# 24GSchematic.net
KiCad netlist of a schematic drawn in Altium Designer
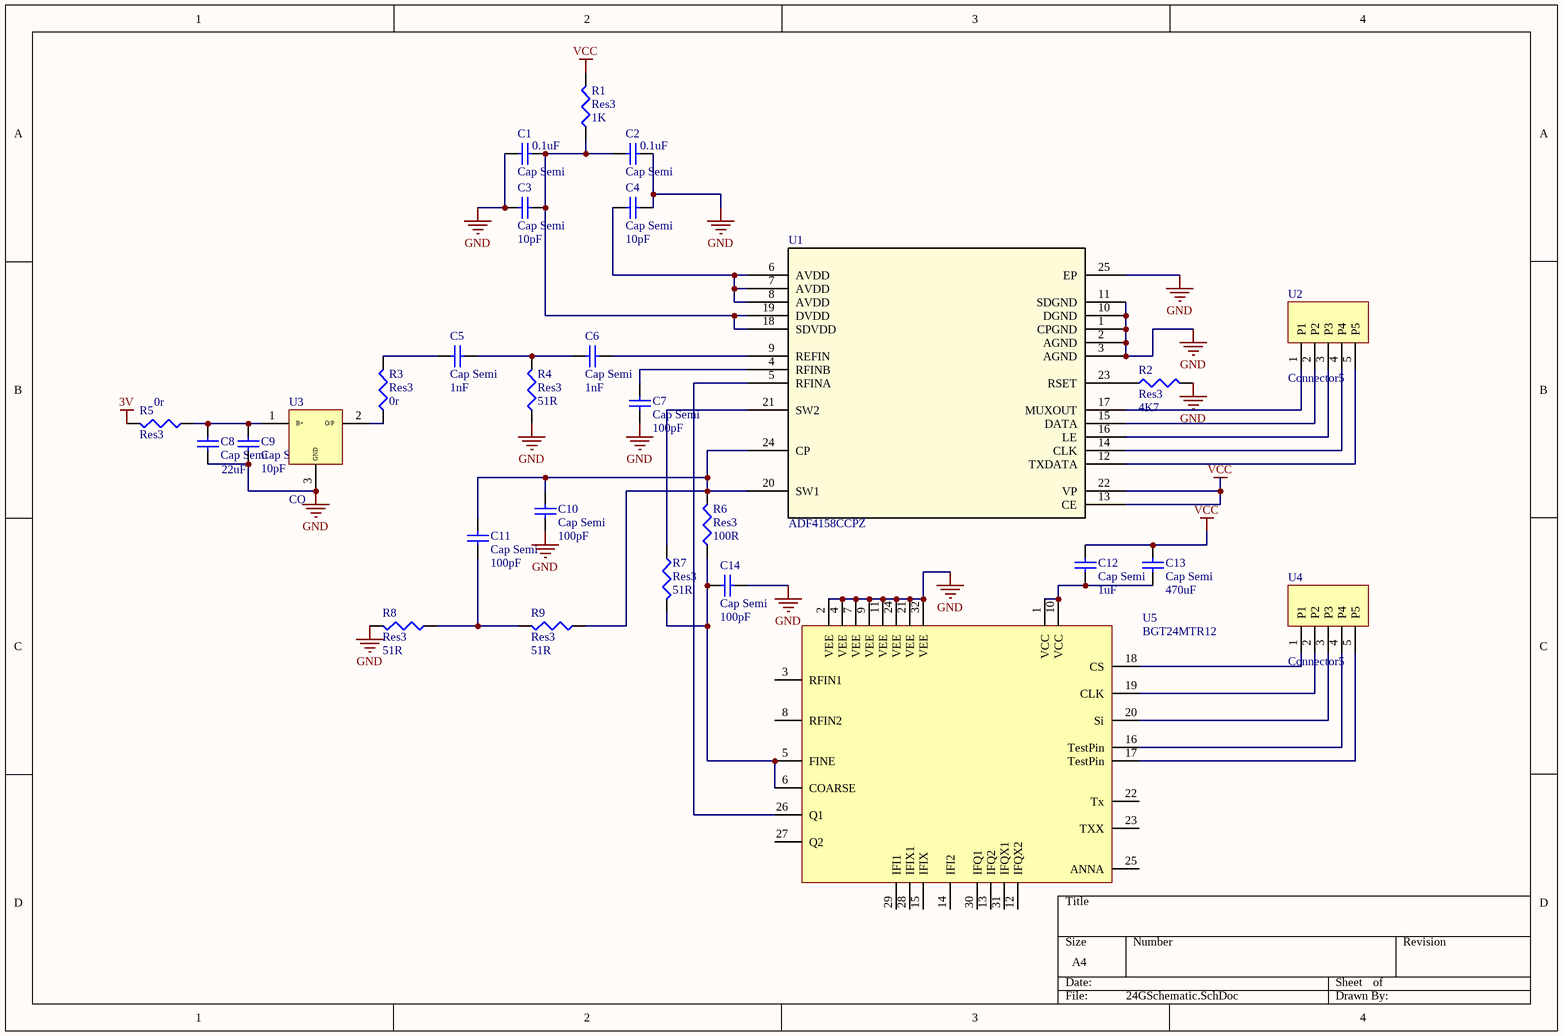
[diagram p0: 24GSchematic.SchDoc]

(export (version "E")
  (design (tool "Eeschema 10.0.6"))
  (components
    (comp (ref "C1")
      (value "Cap Semi")
      (footprint "1608[0603]")
      (description "Capacitor (Semiconductor SIM Model)")
      (fields (field (name "ALTIUM_VALUE") "0.1uF") (field (name "PUBLISHER") "Altium Limited"))
      (libsource (lib "Miscellaneous Devices") (part "Cap Semi"))
    )
    (comp (ref "C2")
      (value "Cap Semi")
      (footprint "1608[0603]")
      (description "Capacitor (Semiconductor SIM Model)")
      (fields (field (name "ALTIUM_VALUE") "0.1uF") (field (name "PUBLISHER") "Altium Limited"))
      (libsource (lib "Miscellaneous Devices") (part "Cap Semi"))
    )
    (comp (ref "C3")
      (value "Cap Semi")
      (footprint "1608[0603]")
      (description "Capacitor (Semiconductor SIM Model)")
      (fields (field (name "ALTIUM_VALUE") "10pF") (field (name "PUBLISHER") "Altium Limited"))
      (libsource (lib "Miscellaneous Devices") (part "Cap Semi"))
    )
    (comp (ref "C4")
      (value "Cap Semi")
      (footprint "1608[0603]")
      (description "Capacitor (Semiconductor SIM Model)")
      (fields (field (name "ALTIUM_VALUE") "10pF") (field (name "PUBLISHER") "Altium Limited"))
      (libsource (lib "Miscellaneous Devices") (part "Cap Semi"))
    )
    (comp (ref "C5")
      (value "Cap Semi")
      (footprint "1608[0603]")
      (description "Capacitor (Semiconductor SIM Model)")
      (fields (field (name "ALTIUM_VALUE") "1nF") (field (name "PUBLISHER") "Altium Limited"))
      (libsource (lib "Miscellaneous Devices") (part "Cap Semi"))
    )
    (comp (ref "C6")
      (value "Cap Semi")
      (footprint "1608[0603]")
      (description "Capacitor (Semiconductor SIM Model)")
      (fields (field (name "ALTIUM_VALUE") "1nF") (field (name "PUBLISHER") "Altium Limited"))
      (libsource (lib "Miscellaneous Devices") (part "Cap Semi"))
    )
    (comp (ref "C7")
      (value "Cap Semi")
      (footprint "1608[0603]")
      (description "Capacitor (Semiconductor SIM Model)")
      (fields (field (name "ALTIUM_VALUE") "100pF") (field (name "PUBLISHER") "Altium Limited"))
      (libsource (lib "Miscellaneous Devices") (part "Cap Semi"))
    )
    (comp (ref "C8")
      (value "Cap Semi")
      (footprint "1608[0603]")
      (description "Capacitor (Semiconductor SIM Model)")
      (fields (field (name "ALTIUM_VALUE") "22uF") (field (name "PUBLISHER") "Altium Limited"))
      (libsource (lib "Miscellaneous Devices") (part "Cap Semi"))
    )
    (comp (ref "C9")
      (value "Cap Semi")
      (footprint "1608[0603]")
      (description "Capacitor (Semiconductor SIM Model)")
      (fields (field (name "ALTIUM_VALUE") "10pF") (field (name "PUBLISHER") "Altium Limited"))
      (libsource (lib "Miscellaneous Devices") (part "Cap Semi"))
    )
    (comp (ref "C10")
      (value "Cap Semi")
      (footprint "1608[0603]")
      (description "Capacitor (Semiconductor SIM Model)")
      (fields (field (name "ALTIUM_VALUE") "100pF") (field (name "PUBLISHER") "Altium Limited"))
      (libsource (lib "Miscellaneous Devices") (part "Cap Semi"))
    )
    (comp (ref "C11")
      (value "Cap Semi")
      (footprint "1608[0603]")
      (description "Capacitor (Semiconductor SIM Model)")
      (fields (field (name "ALTIUM_VALUE") "100pF") (field (name "PUBLISHER") "Altium Limited"))
      (libsource (lib "Miscellaneous Devices") (part "Cap Semi"))
    )
    (comp (ref "C12")
      (value "Cap Semi")
      (footprint "1608[0603]")
      (description "Capacitor (Semiconductor SIM Model)")
      (fields (field (name "ALTIUM_VALUE") "1uF") (field (name "PUBLISHER") "Altium Limited"))
      (libsource (lib "Miscellaneous Devices") (part "Cap Semi"))
    )
    (comp (ref "C13")
      (value "Cap Semi")
      (footprint "1608[0603]")
      (description "Capacitor (Semiconductor SIM Model)")
      (fields (field (name "ALTIUM_VALUE") "470uF") (field (name "PUBLISHER") "Altium Limited"))
      (libsource (lib "Miscellaneous Devices") (part "Cap Semi"))
    )
    (comp (ref "C14")
      (value "Cap Semi")
      (footprint "1608[0603]")
      (description "Capacitor (Semiconductor SIM Model)")
      (fields (field (name "ALTIUM_VALUE") "100pF") (field (name "PUBLISHER") "Altium Limited"))
      (libsource (lib "Miscellaneous Devices") (part "Cap Semi"))
    )
    (comp (ref "R1")
      (value "Res3")
      (footprint "J1-0603")
      (description "Resistor")
      (fields (field (name "ALTIUM_VALUE") "1K") (field (name "PUBLISHER") "Altium Limited"))
      (libsource (lib "Miscellaneous Devices") (part "Res3"))
    )
    (comp (ref "R2")
      (value "Res3")
      (footprint "J1-0603")
      (description "Resistor")
      (fields (field (name "ALTIUM_VALUE") "4K7") (field (name "PUBLISHER") "Altium Limited"))
      (libsource (lib "Miscellaneous Devices") (part "Res3"))
    )
    (comp (ref "R3")
      (value "Res3")
      (footprint "J1-0603")
      (description "Resistor")
      (fields (field (name "ALTIUM_VALUE") "0r") (field (name "PUBLISHER") "Altium Limited"))
      (libsource (lib "Miscellaneous Devices") (part "Res3"))
    )
    (comp (ref "R4")
      (value "Res3")
      (footprint "J1-0603")
      (description "Resistor")
      (fields (field (name "ALTIUM_VALUE") "51R") (field (name "PUBLISHER") "Altium Limited"))
      (libsource (lib "Miscellaneous Devices") (part "Res3"))
    )
    (comp (ref "R5")
      (value "Res3")
      (footprint "J1-0603")
      (description "Resistor")
      (fields (field (name "ALTIUM_VALUE") "0r") (field (name "PUBLISHER") "Altium Limited"))
      (libsource (lib "Miscellaneous Devices") (part "Res3"))
    )
    (comp (ref "R6")
      (value "Res3")
      (footprint "J1-0603")
      (description "Resistor")
      (fields (field (name "ALTIUM_VALUE") "100R") (field (name "PUBLISHER") "Altium Limited"))
      (libsource (lib "Miscellaneous Devices") (part "Res3"))
    )
    (comp (ref "R7")
      (value "Res3")
      (footprint "J1-0603")
      (description "Resistor")
      (fields (field (name "ALTIUM_VALUE") "51R") (field (name "PUBLISHER") "Altium Limited"))
      (libsource (lib "Miscellaneous Devices") (part "Res3"))
    )
    (comp (ref "R8")
      (value "Res3")
      (footprint "J1-0603")
      (description "Resistor")
      (fields (field (name "ALTIUM_VALUE") "51R") (field (name "PUBLISHER") "Altium Limited"))
      (libsource (lib "Miscellaneous Devices") (part "Res3"))
    )
    (comp (ref "R9")
      (value "Res3")
      (footprint "J1-0603")
      (description "Resistor")
      (fields (field (name "ALTIUM_VALUE") "51R") (field (name "PUBLISHER") "Altium Limited"))
      (libsource (lib "Miscellaneous Devices") (part "Res3"))
    )
    (comp (ref "U1")
      (value "ADF4158CCPZ")
      (footprint "CP_24_7")
      (description "Imported")
      (libsource (lib "2016-06-22_14-55-40") (part "ADF4158CCPZ"))
    )
    (comp (ref "U2")
      (value "Connector5")
      (footprint "Connector5P - duplicate")
      (libsource (lib "2016-06-22_14-55-40") (part "Connector5"))
    )
    (comp (ref "U3")
      (value "CO")
      (footprint "FOX801BE-100")
      (libsource (lib "2016-06-22_14-55-40") (part "CO"))
    )
    (comp (ref "U4")
      (value "Connector5")
      (footprint "Connector5P - duplicate")
      (libsource (lib "2016-06-22_14-55-40") (part "Connector5"))
    )
    (comp (ref "U5")
      (value "BGT24MTR12")
      (footprint "QFN50P540X440X90_HS-33N")
      (libsource (lib "2016-06-22_14-55-40") (part "BGT24MTR12"))
    )
  )
  (nets
    (net (code "1") (name "3V") (class "Default")
      (node (ref "R5") (pin "2") (pinfunction "2_2") (pintype "passive"))
    )
    (net (code "2") (name "GND") (class "Default")
      (node (ref "C1") (pin "1") (pinfunction "1_1") (pintype "passive"))
      (node (ref "C10") (pin "2") (pinfunction "2_2") (pintype "passive"))
      (node (ref "C14") (pin "1") (pinfunction "1_1") (pintype "passive"))
      (node (ref "C2") (pin "2") (pinfunction "2_2") (pintype "passive"))
      (node (ref "C3") (pin "1") (pinfunction "1_1") (pintype "passive"))
      (node (ref "C4") (pin "2") (pinfunction "2_2") (pintype "passive"))
      (node (ref "C7") (pin "1") (pinfunction "1_1") (pintype "passive"))
      (node (ref "C8") (pin "1") (pinfunction "1_1") (pintype "passive"))
      (node (ref "C9") (pin "1") (pinfunction "1_1") (pintype "passive"))
      (node (ref "R2") (pin "2") (pinfunction "2_2") (pintype "passive"))
      (node (ref "R4") (pin "1") (pinfunction "1_1") (pintype "passive"))
      (node (ref "R8") (pin "2") (pinfunction "2_2") (pintype "passive"))
      (node (ref "U1") (pin "1") (pinfunction "CPGND_1") (pintype "passive"))
      (node (ref "U1") (pin "10") (pinfunction "DGND_10") (pintype "passive"))
      (node (ref "U1") (pin "11") (pinfunction "SDGND_11") (pintype "passive"))
      (node (ref "U1") (pin "2") (pinfunction "AGND_2") (pintype "passive"))
      (node (ref "U1") (pin "25") (pinfunction "EP_25") (pintype "passive"))
      (node (ref "U1") (pin "3") (pinfunction "AGND_3") (pintype "passive"))
      (node (ref "U3") (pin "3") (pinfunction "GND_3") (pintype "passive"))
      (node (ref "U5") (pin "11") (pinfunction "VEE_11") (pintype "passive"))
      (node (ref "U5") (pin "2") (pinfunction "VEE_2") (pintype "passive"))
      (node (ref "U5") (pin "21") (pinfunction "VEE_21") (pintype "passive"))
      (node (ref "U5") (pin "24") (pinfunction "VEE_24") (pintype "passive"))
      (node (ref "U5") (pin "32") (pinfunction "VEE_32") (pintype "passive"))
      (node (ref "U5") (pin "4") (pinfunction "VEE_4") (pintype "passive"))
      (node (ref "U5") (pin "7") (pinfunction "VEE_7") (pintype "passive"))
      (node (ref "U5") (pin "9") (pinfunction "VEE_9") (pintype "passive"))
    )
    (net (code "3") (name "Net-(C4-Pad1)") (class "Default")
      (node (ref "C4") (pin "1") (pinfunction "1_1") (pintype "passive"))
      (node (ref "U1") (pin "6") (pinfunction "AVDD_6") (pintype "passive"))
      (node (ref "U1") (pin "7") (pinfunction "AVDD_7") (pintype "passive"))
      (node (ref "U1") (pin "8") (pinfunction "AVDD_8") (pintype "passive"))
    )
    (net (code "4") (name "Net-(C5-Pad1)") (class "Default")
      (node (ref "C5") (pin "1") (pinfunction "1_1") (pintype "passive"))
      (node (ref "R3") (pin "2") (pinfunction "2_2") (pintype "passive"))
    )
    (net (code "5") (name "Net-(C5-Pad2)") (class "Default")
      (node (ref "C5") (pin "2") (pinfunction "2_2") (pintype "passive"))
      (node (ref "C6") (pin "1") (pinfunction "1_1") (pintype "passive"))
      (node (ref "R4") (pin "2") (pinfunction "2_2") (pintype "passive"))
    )
    (net (code "6") (name "Net-(C11-Pad1)") (class "Default")
      (node (ref "C11") (pin "1") (pinfunction "1_1") (pintype "passive"))
      (node (ref "R8") (pin "1") (pinfunction "1_1") (pintype "passive"))
      (node (ref "R9") (pin "2") (pinfunction "2_2") (pintype "passive"))
    )
    (net (code "7") (name "Net-(C12-Pad2)") (class "Default")
      (node (ref "C12") (pin "2") (pinfunction "2_2") (pintype "passive"))
      (node (ref "C13") (pin "2") (pinfunction "2_2") (pintype "passive"))
      (node (ref "U5") (pin "1") (pinfunction "VCC_1") (pintype "passive"))
      (node (ref "U5") (pin "10") (pinfunction "VCC_10") (pintype "passive"))
    )
    (net (code "8") (name "Net-(U1-CLK)") (class "Default")
      (node (ref "U1") (pin "14") (pinfunction "CLK_14") (pintype "passive"))
      (node (ref "U2") (pin "4") (pinfunction "P4_4") (pintype "passive"))
    )
    (net (code "9") (name "Net-(U1-CP)") (class "Default")
      (node (ref "C10") (pin "1") (pinfunction "1_1") (pintype "passive"))
      (node (ref "C11") (pin "2") (pinfunction "2_2") (pintype "passive"))
      (node (ref "R6") (pin "2") (pinfunction "2_2") (pintype "passive"))
      (node (ref "R9") (pin "1") (pinfunction "1_1") (pintype "passive"))
      (node (ref "U1") (pin "20") (pinfunction "SW1_20") (pintype "passive"))
      (node (ref "U1") (pin "24") (pinfunction "CP_24") (pintype "passive"))
    )
    (net (code "10") (name "Net-(U1-DATA)") (class "Default")
      (node (ref "U1") (pin "15") (pinfunction "DATA_15") (pintype "passive"))
      (node (ref "U2") (pin "2") (pinfunction "P2_2") (pintype "passive"))
    )
    (net (code "11") (name "Net-(U1-DVDD)") (class "Default")
      (node (ref "C1") (pin "2") (pinfunction "2_2") (pintype "passive"))
      (node (ref "C2") (pin "1") (pinfunction "1_1") (pintype "passive"))
      (node (ref "C3") (pin "2") (pinfunction "2_2") (pintype "passive"))
      (node (ref "R1") (pin "2") (pinfunction "2_2") (pintype "passive"))
      (node (ref "U1") (pin "18") (pinfunction "SDVDD_18") (pintype "passive"))
      (node (ref "U1") (pin "19") (pinfunction "DVDD_19") (pintype "passive"))
    )
    (net (code "12") (name "Net-(U1-LE)") (class "Default")
      (node (ref "U1") (pin "16") (pinfunction "LE_16") (pintype "passive"))
      (node (ref "U2") (pin "3") (pinfunction "P3_3") (pintype "passive"))
    )
    (net (code "13") (name "Net-(U1-MUXOUT)") (class "Default")
      (node (ref "U1") (pin "17") (pinfunction "MUXOUT_17") (pintype "passive"))
      (node (ref "U2") (pin "1") (pinfunction "P1_1") (pintype "passive"))
    )
    (net (code "14") (name "Net-(U1-REFIN)") (class "Default")
      (node (ref "C6") (pin "2") (pinfunction "2_2") (pintype "passive"))
      (node (ref "U1") (pin "9") (pinfunction "REFIN_9") (pintype "passive"))
    )
    (net (code "15") (name "Net-(U1-RFINA)") (class "Default")
      (node (ref "U1") (pin "5") (pinfunction "RFINA_5") (pintype "passive"))
      (node (ref "U5") (pin "26") (pinfunction "Q1_26") (pintype "passive"))
    )
    (net (code "16") (name "Net-(U1-RFINB)") (class "Default")
      (node (ref "C7") (pin "2") (pinfunction "2_2") (pintype "passive"))
      (node (ref "U1") (pin "4") (pinfunction "RFINB_4") (pintype "passive"))
    )
    (net (code "17") (name "Net-(U1-RSET)") (class "Default")
      (node (ref "R2") (pin "1") (pinfunction "1_1") (pintype "passive"))
      (node (ref "U1") (pin "23") (pinfunction "RSET_23") (pintype "passive"))
    )
    (net (code "18") (name "Net-(U1-SW2)") (class "Default")
      (node (ref "R7") (pin "1") (pinfunction "1_1") (pintype "passive"))
      (node (ref "U1") (pin "21") (pinfunction "SW2_21") (pintype "passive"))
    )
    (net (code "19") (name "Net-(U1-TXDATA)") (class "Default")
      (node (ref "U1") (pin "12") (pinfunction "TXDATA_12") (pintype "passive"))
      (node (ref "U2") (pin "5") (pinfunction "P5_5") (pintype "passive"))
    )
    (net (code "20") (name "Net-(U3-B+)") (class "Default")
      (node (ref "C8") (pin "2") (pinfunction "2_2") (pintype "passive"))
      (node (ref "C9") (pin "2") (pinfunction "2_2") (pintype "passive"))
      (node (ref "R5") (pin "1") (pinfunction "1_1") (pintype "passive"))
      (node (ref "U3") (pin "1") (pinfunction "B+_1") (pintype "passive"))
    )
    (net (code "21") (name "Net-(U3-O{slash}P)") (class "Default")
      (node (ref "R3") (pin "1") (pinfunction "1_1") (pintype "passive"))
      (node (ref "U3") (pin "2") (pinfunction "O/P_2") (pintype "passive"))
    )
    (net (code "22") (name "Net-(U4-P1)") (class "Default")
      (node (ref "U4") (pin "1") (pinfunction "P1_1") (pintype "passive"))
      (node (ref "U5") (pin "18") (pinfunction "CS_18") (pintype "passive"))
    )
    (net (code "23") (name "Net-(U4-P2)") (class "Default")
      (node (ref "U4") (pin "2") (pinfunction "P2_2") (pintype "passive"))
      (node (ref "U5") (pin "19") (pinfunction "CLK_19") (pintype "passive"))
    )
    (net (code "24") (name "Net-(U4-P3)") (class "Default")
      (node (ref "U4") (pin "3") (pinfunction "P3_3") (pintype "passive"))
      (node (ref "U5") (pin "20") (pinfunction "Si_20") (pintype "passive"))
    )
    (net (code "25") (name "Net-(U4-P4)") (class "Default")
      (node (ref "U4") (pin "4") (pinfunction "P4_4") (pintype "passive"))
      (node (ref "U5") (pin "16") (pinfunction "TestPin_16") (pintype "passive"))
    )
    (net (code "26") (name "Net-(U4-P5)") (class "Default")
      (node (ref "U4") (pin "5") (pinfunction "P5_5") (pintype "passive"))
      (node (ref "U5") (pin "17") (pinfunction "TestPin_17") (pintype "passive"))
    )
    (net (code "27") (name "Net-(U5-COARSE)") (class "Default")
      (node (ref "C14") (pin "2") (pinfunction "2_2") (pintype "passive"))
      (node (ref "R6") (pin "1") (pinfunction "1_1") (pintype "passive"))
      (node (ref "R7") (pin "2") (pinfunction "2_2") (pintype "passive"))
      (node (ref "U5") (pin "5") (pinfunction "FINE_5") (pintype "passive"))
      (node (ref "U5") (pin "6") (pinfunction "COARSE_6") (pintype "passive"))
    )
    (net (code "28") (name "VCC") (class "Default")
      (node (ref "C12") (pin "1") (pinfunction "1_1") (pintype "passive"))
      (node (ref "C13") (pin "1") (pinfunction "1_1") (pintype "passive"))
      (node (ref "R1") (pin "1") (pinfunction "1_1") (pintype "passive"))
      (node (ref "U1") (pin "13") (pinfunction "CE_13") (pintype "passive"))
      (node (ref "U1") (pin "22") (pinfunction "VP_22") (pintype "passive"))
    )
    (net (code "29") (name "unconnected-(U5-ANNA-Pad25)") (class "Default")
      (node (ref "U5") (pin "25") (pinfunction "ANNA_25") (pintype "passive"))
    )
    (net (code "30") (name "unconnected-(U5-IFI1-Pad29)") (class "Default")
      (node (ref "U5") (pin "29") (pinfunction "IFI1_29") (pintype "passive"))
    )
    (net (code "31") (name "unconnected-(U5-IFI2-Pad14)") (class "Default")
      (node (ref "U5") (pin "14") (pinfunction "IFI2_14") (pintype "passive"))
    )
    (net (code "32") (name "unconnected-(U5-IFIX-Pad15)") (class "Default")
      (node (ref "U5") (pin "15") (pinfunction "IFIX_15") (pintype "passive"))
    )
    (net (code "33") (name "unconnected-(U5-IFIX1-Pad28)") (class "Default")
      (node (ref "U5") (pin "28") (pinfunction "IFIX1_28") (pintype "passive"))
    )
    (net (code "34") (name "unconnected-(U5-IFQ1-Pad30)") (class "Default")
      (node (ref "U5") (pin "30") (pinfunction "IFQ1_30") (pintype "passive"))
    )
    (net (code "35") (name "unconnected-(U5-IFQ2-Pad13)") (class "Default")
      (node (ref "U5") (pin "13") (pinfunction "IFQ2_13") (pintype "passive"))
    )
    (net (code "36") (name "unconnected-(U5-IFQX1-Pad31)") (class "Default")
      (node (ref "U5") (pin "31") (pinfunction "IFQX1_31") (pintype "passive"))
    )
    (net (code "37") (name "unconnected-(U5-IFQX2-Pad12)") (class "Default")
      (node (ref "U5") (pin "12") (pinfunction "IFQX2_12") (pintype "passive"))
    )
    (net (code "38") (name "unconnected-(U5-Q2-Pad27)") (class "Default")
      (node (ref "U5") (pin "27") (pinfunction "Q2_27") (pintype "passive"))
    )
    (net (code "39") (name "unconnected-(U5-RFIN1-Pad3)") (class "Default")
      (node (ref "U5") (pin "3") (pinfunction "RFIN1_3") (pintype "passive"))
    )
    (net (code "40") (name "unconnected-(U5-RFIN2-Pad8)") (class "Default")
      (node (ref "U5") (pin "8") (pinfunction "RFIN2_8") (pintype "passive"))
    )
    (net (code "41") (name "unconnected-(U5-TXX-Pad23)") (class "Default")
      (node (ref "U5") (pin "23") (pinfunction "TXX_23") (pintype "passive"))
    )
    (net (code "42") (name "unconnected-(U5-Tx-Pad22)") (class "Default")
      (node (ref "U5") (pin "22") (pinfunction "Tx_22") (pintype "passive"))
    )
  )
)
